# connectors.net
KiCad netlist of a schematic drawn in Altium Designer
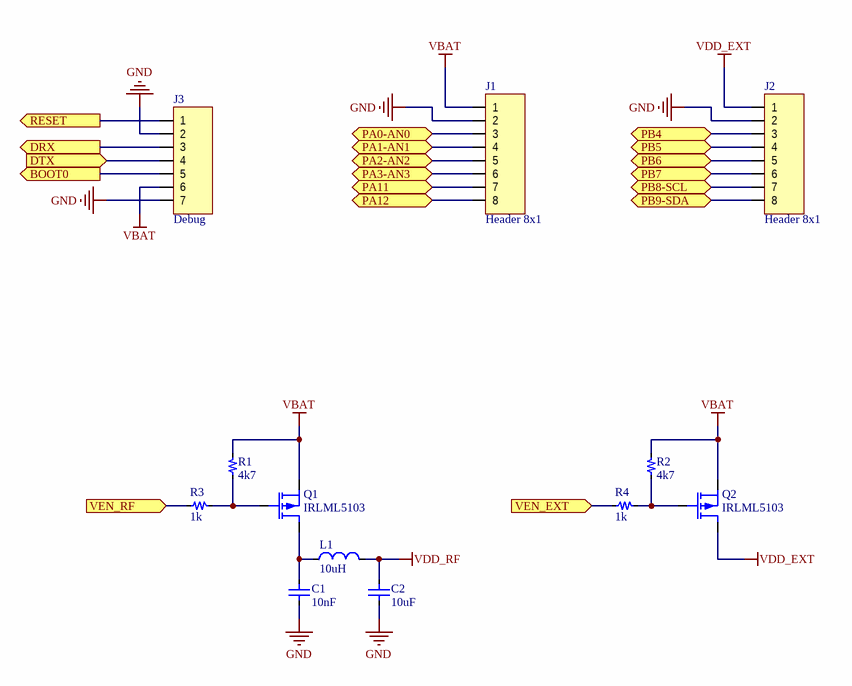
[diagram p0: connectors.SchDoc]

(export (version "E")
  (design (tool "Eeschema 10.0.6"))
  (components
    (comp (ref "C1")
      (value "10nF")
      (footprint "0402_[1005]")
      (description "Capacitor")
      (libsource (lib "Discrete") (part "C"))
    )
    (comp (ref "C2")
      (value "10uF")
      (footprint "0603_[1608]")
      (description "Capacitor")
      (libsource (lib "Discrete") (part "C"))
    )
    (comp (ref "J1")
      (value "Header 8x1")
      (footprint "HDR8x1-H")
      (description "Pin header, 8x1")
      (libsource (lib "Connectors") (part "HDR 8x1"))
    )
    (comp (ref "J2")
      (value "Header 8x1")
      (footprint "HDR8x1-H")
      (description "Pin header, 8x1")
      (libsource (lib "Connectors") (part "HDR 8x1"))
    )
    (comp (ref "J3")
      (value "Debug")
      (footprint "HDR7x1-H")
      (description "Pin header, 7x1")
      (libsource (lib "Connectors") (part "HDR 7x1"))
    )
    (comp (ref "L1")
      (value "10uH")
      (footprint "1206_[3216]")
      (description "Inductor")
      (libsource (lib "Discrete") (part "L"))
    )
    (comp (ref "Q1")
      (value "IRLML5103")
      (footprint "SOT-23-MOS")
      (description "P-channel MOSFET")
      (libsource (lib "Discrete") (part "PMOS"))
    )
    (comp (ref "Q2")
      (value "IRLML5103")
      (footprint "SOT-23-MOS")
      (description "P-channel MOSFET")
      (libsource (lib "Discrete") (part "PMOS"))
    )
    (comp (ref "R1")
      (value "4k7")
      (footprint "0402_[1005]")
      (description "Resistor")
      (libsource (lib "Discrete") (part "R"))
    )
    (comp (ref "R2")
      (value "4k7")
      (footprint "0402_[1005]")
      (description "Resistor")
      (libsource (lib "Discrete") (part "R"))
    )
    (comp (ref "R3")
      (value "1k")
      (footprint "0402_[1005]")
      (description "Resistor")
      (libsource (lib "Discrete") (part "R"))
    )
    (comp (ref "R4")
      (value "1k")
      (footprint "0402_[1005]")
      (description "Resistor")
      (libsource (lib "Discrete") (part "R"))
    )
  )
  (nets
    (net (code "1") (name "/BOOT0") (class "Default")
      (node (ref "J3") (pin "5") (pinfunction "5_5") (pintype "passive"))
    )
    (net (code "2") (name "/DRX") (class "Default")
      (node (ref "J3") (pin "3") (pinfunction "3_3") (pintype "passive"))
    )
    (net (code "3") (name "/DTX") (class "Default")
      (node (ref "J3") (pin "4") (pinfunction "4_4") (pintype "passive"))
    )
    (net (code "4") (name "/PA0-AN0") (class "Default")
      (node (ref "J1") (pin "3") (pinfunction "3_3") (pintype "passive"))
    )
    (net (code "5") (name "/PA1-AN1") (class "Default")
      (node (ref "J1") (pin "4") (pinfunction "4_4") (pintype "passive"))
    )
    (net (code "6") (name "/PA2-AN2") (class "Default")
      (node (ref "J1") (pin "5") (pinfunction "5_5") (pintype "passive"))
    )
    (net (code "7") (name "/PA3-AN3") (class "Default")
      (node (ref "J1") (pin "6") (pinfunction "6_6") (pintype "passive"))
    )
    (net (code "8") (name "/PA11") (class "Default")
      (node (ref "J1") (pin "7") (pinfunction "7_7") (pintype "passive"))
    )
    (net (code "9") (name "/PA12") (class "Default")
      (node (ref "J1") (pin "8") (pinfunction "8_8") (pintype "passive"))
    )
    (net (code "10") (name "/PB4") (class "Default")
      (node (ref "J2") (pin "3") (pinfunction "3_3") (pintype "passive"))
    )
    (net (code "11") (name "/PB5") (class "Default")
      (node (ref "J2") (pin "4") (pinfunction "4_4") (pintype "passive"))
    )
    (net (code "12") (name "/PB6") (class "Default")
      (node (ref "J2") (pin "5") (pinfunction "5_5") (pintype "passive"))
    )
    (net (code "13") (name "/PB7") (class "Default")
      (node (ref "J2") (pin "6") (pinfunction "6_6") (pintype "passive"))
    )
    (net (code "14") (name "/PB8-SCL") (class "Default")
      (node (ref "J2") (pin "7") (pinfunction "7_7") (pintype "passive"))
    )
    (net (code "15") (name "/PB9-SDA") (class "Default")
      (node (ref "J2") (pin "8") (pinfunction "8_8") (pintype "passive"))
    )
    (net (code "16") (name "/RESET") (class "Default")
      (node (ref "J3") (pin "1") (pinfunction "1_1") (pintype "passive"))
    )
    (net (code "17") (name "/VEN_EXT") (class "Default")
      (node (ref "R4") (pin "1") (pinfunction "1_1") (pintype "passive"))
    )
    (net (code "18") (name "/VEN_RF") (class "Default")
      (node (ref "R3") (pin "1") (pinfunction "1_1") (pintype "passive"))
    )
    (net (code "19") (name "GND") (class "Default")
      (node (ref "C1") (pin "1") (pinfunction "1_1") (pintype "passive"))
      (node (ref "C2") (pin "1") (pinfunction "1_1") (pintype "passive"))
      (node (ref "J1") (pin "2") (pinfunction "2_2") (pintype "passive"))
      (node (ref "J2") (pin "2") (pinfunction "2_2") (pintype "passive"))
      (node (ref "J3") (pin "2") (pinfunction "2_2") (pintype "passive"))
      (node (ref "J3") (pin "7") (pinfunction "7_7") (pintype "passive"))
    )
    (net (code "20") (name "Net-(Q1-D)") (class "Default")
      (node (ref "C1") (pin "2") (pinfunction "2_2") (pintype "passive"))
      (node (ref "L1") (pin "1") (pinfunction "1_1") (pintype "passive"))
      (node (ref "Q1") (pin "2") (pinfunction "D_2") (pintype "passive"))
    )
    (net (code "21") (name "Net-(Q1-G)") (class "Default")
      (node (ref "Q1") (pin "1") (pinfunction "G_1") (pintype "passive"))
      (node (ref "R1") (pin "1") (pinfunction "1_1") (pintype "passive"))
      (node (ref "R3") (pin "2") (pinfunction "2_2") (pintype "passive"))
    )
    (net (code "22") (name "Net-(Q2-G)") (class "Default")
      (node (ref "Q2") (pin "1") (pinfunction "G_1") (pintype "passive"))
      (node (ref "R2") (pin "1") (pinfunction "1_1") (pintype "passive"))
      (node (ref "R4") (pin "2") (pinfunction "2_2") (pintype "passive"))
    )
    (net (code "23") (name "VBAT") (class "Default")
      (node (ref "J1") (pin "1") (pinfunction "1_1") (pintype "passive"))
      (node (ref "J3") (pin "6") (pinfunction "6_6") (pintype "passive"))
      (node (ref "Q1") (pin "3") (pinfunction "S_3") (pintype "passive"))
      (node (ref "Q2") (pin "3") (pinfunction "S_3") (pintype "passive"))
      (node (ref "R1") (pin "2") (pinfunction "2_2") (pintype "passive"))
      (node (ref "R2") (pin "2") (pinfunction "2_2") (pintype "passive"))
    )
    (net (code "24") (name "VDD_EXT") (class "Default")
      (node (ref "J2") (pin "1") (pinfunction "1_1") (pintype "passive"))
      (node (ref "Q2") (pin "2") (pinfunction "D_2") (pintype "passive"))
    )
    (net (code "25") (name "VDD_RF") (class "Default")
      (node (ref "C2") (pin "2") (pinfunction "2_2") (pintype "passive"))
      (node (ref "L1") (pin "2") (pinfunction "2_2") (pintype "passive"))
    )
  )
)
